# board2_schematic.net
KiCad netlist of a schematic drawn in Altium Designer
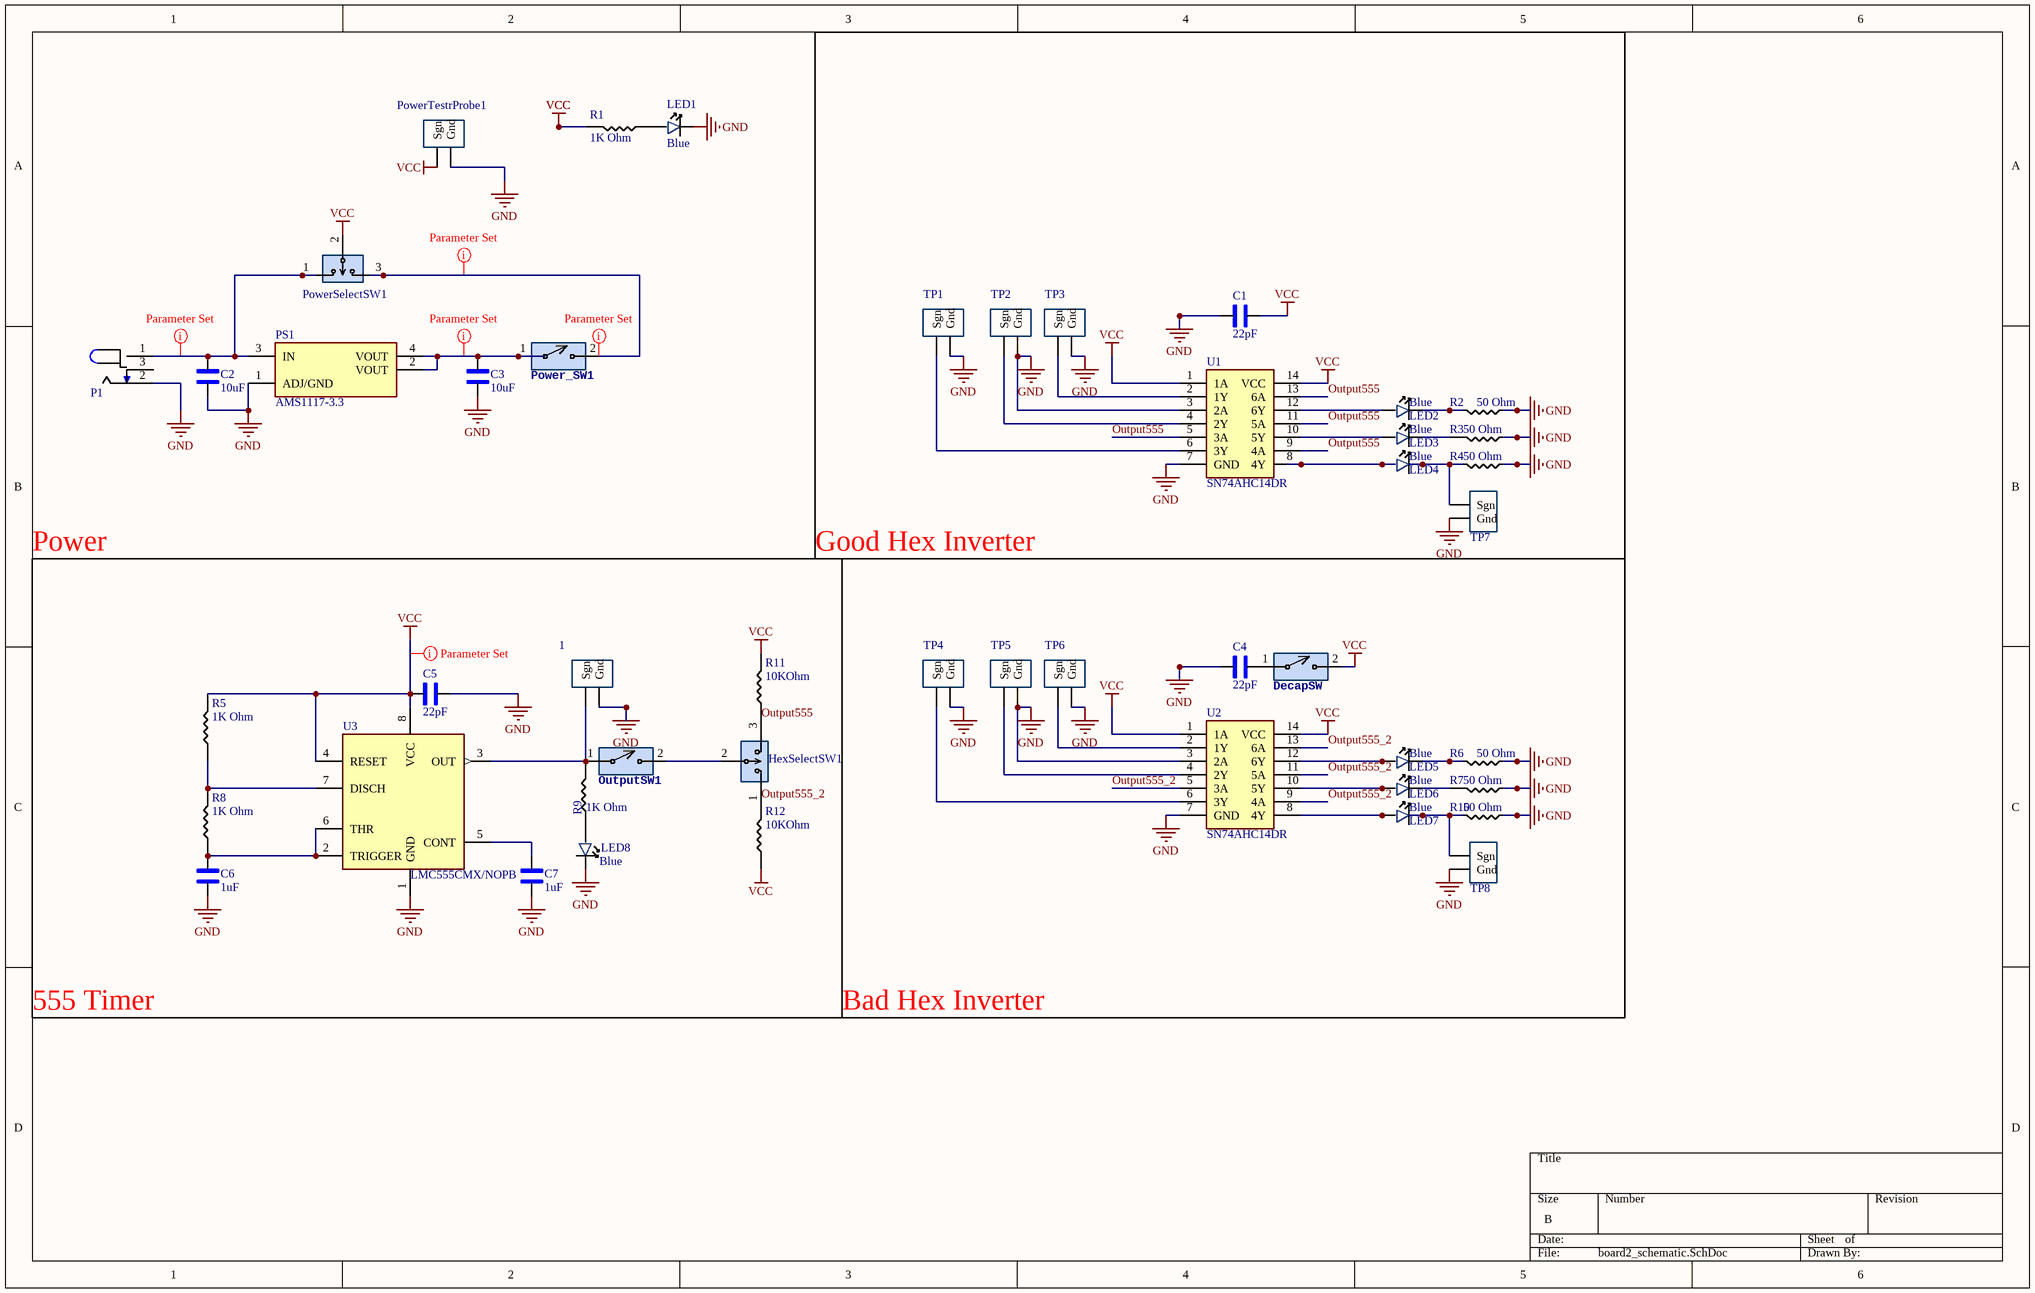
[diagram p0: board2_schematic.SchDoc]

(export (version "E")
  (design (tool "Eeschema 10.0.6"))
  (components
    (comp (ref "1")
      (value "10x Probe TP")
      (footprint "TP10x_Probe")
      (description "Test Point 300 mil centers")
      (libsource (lib "") (part "TP_10x_Probe_1"))
    )
    (comp (ref "C1")
      (value "22pF")
      (footprint "1206_Passive_Capacitor")
      (description "22pF ±5% 1kV C0G 1206 Multilayer Ceramic Capacitors MLCC - SMD/SMT RoHS")
      (fields (field (name "LCSC PART#") "C107174") (field (name "MFR PART #") "CC1206JKNPOCBN220"))
      (libsource (lib "ECEN5730Lib_2023_05_DS") (part "C_22pF_1206"))
    )
    (comp (ref "C2")
      (value "10uF")
      (footprint "1206_Passive_Capacitor")
      (description "10uF ±10% 50V X5R 1206 Multilayer Ceramic Capacitors MLCC - SMD/SMT RoHS")
      (fields (field (name "LCSC PART#") "C13585") (field (name "MFR PART #") "CL31A106KBHNNNE"))
      (libsource (lib "ECEN5730Lib_2023_05_DS") (part "C_10uF_1206"))
    )
    (comp (ref "C3")
      (value "10uF")
      (footprint "1206_Passive_Capacitor")
      (description "10uF ±10% 50V X5R 1206 Multilayer Ceramic Capacitors MLCC - SMD/SMT RoHS")
      (fields (field (name "LCSC PART#") "C13585") (field (name "MFR PART #") "CL31A106KBHNNNE"))
      (libsource (lib "ECEN5730Lib_2023_05_DS") (part "C_10uF_1206"))
    )
    (comp (ref "C4")
      (value "22pF")
      (footprint "1206_Passive_Capacitor")
      (description "22pF ±5% 1kV C0G 1206 Multilayer Ceramic Capacitors MLCC - SMD/SMT RoHS")
      (fields (field (name "LCSC PART#") "C107174") (field (name "MFR PART #") "CC1206JKNPOCBN220"))
      (libsource (lib "ECEN5730Lib_2023_05_DS") (part "C_22pF_1206"))
    )
    (comp (ref "C5")
      (value "22pF")
      (footprint "1206_Passive_Capacitor")
      (description "22pF ±5% 1kV C0G 1206 Multilayer Ceramic Capacitors MLCC - SMD/SMT RoHS")
      (fields (field (name "LCSC PART#") "C107174") (field (name "MFR PART #") "CC1206JKNPOCBN220"))
      (libsource (lib "ECEN5730Lib_2023_05_DS") (part "C_22pF_1206"))
    )
    (comp (ref "C6")
      (value "1uF")
      (footprint "1206_Passive_Capacitor")
      (description "MULTILAYER CERAMIC CAPACITORS MLCC - SMD/SMT 1UF 50V 1206 ROHS")
      (fields (field (name "MFR PART #") "CL31B105KBHNNNE") (field (name "LCSC PART#") "C1848"))
      (libsource (lib "ECEN5730Lib_2023_05_DS") (part "C_1uF_1206"))
    )
    (comp (ref "C7")
      (value "1uF")
      (footprint "1206_Passive_Capacitor")
      (description "MULTILAYER CERAMIC CAPACITORS MLCC - SMD/SMT 1UF 50V 1206 ROHS")
      (fields (field (name "MFR PART #") "CL31B105KBHNNNE") (field (name "LCSC PART#") "C1848"))
      (libsource (lib "ECEN5730Lib_2023_05_DS") (part "C_1uF_1206"))
    )
    (comp (ref "DecapSW")
      (value "SW_2Pin_100mil_Switch")
      (footprint "2Pin-Header-Conn")
      (description "2Pin Header")
      (fields (field (name "LCSC PART#") "C124375"))
      (libsource (lib "ECEN5730Lib_2023_05_DS") (part "SW_2Pin_100mil_Switch"))
    )
    (comp (ref "HexSelectSW1")
      (value "PREC003SAAN-RC")
      (footprint "3_PIN_100mil")
      (description "Connector Header Through Hole 3 position 0.100\" (2.54mm)")
      (fields (field (name "LCSC PART#") "C49257"))
      (libsource (lib "ECEN5730Lib_2023_05_DS") (part "SW_3Pin_100mil_Switch"))
    )
    (comp (ref "LED1")
      (value "Blue")
      (footprint "LED_1206")
      (description "blue 1206  Light Emitting Diodes (LED) ROHS")
      (fields (field (name "MFR PART #") "NCD1206B1") (field (name "LCSC PART#") "C130717"))
      (libsource (lib "ECEN5730Lib_2023_05_DS") (part "LED_BLUE_1206"))
    )
    (comp (ref "LED2")
      (value "Blue")
      (footprint "LED_1206")
      (description "blue 1206  Light Emitting Diodes (LED) ROHS")
      (fields (field (name "MFR PART #") "NCD1206B1") (field (name "LCSC PART#") "C130717"))
      (libsource (lib "ECEN5730Lib_2023_05_DS") (part "LED_BLUE_1206"))
    )
    (comp (ref "LED3")
      (value "Blue")
      (footprint "LED_1206")
      (description "blue 1206  Light Emitting Diodes (LED) ROHS")
      (fields (field (name "MFR PART #") "NCD1206B1") (field (name "LCSC PART#") "C130717"))
      (libsource (lib "ECEN5730Lib_2023_05_DS") (part "LED_BLUE_1206"))
    )
    (comp (ref "LED4")
      (value "Blue")
      (footprint "LED_1206")
      (description "blue 1206  Light Emitting Diodes (LED) ROHS")
      (fields (field (name "MFR PART #") "NCD1206B1") (field (name "LCSC PART#") "C130717"))
      (libsource (lib "ECEN5730Lib_2023_05_DS") (part "LED_BLUE_1206"))
    )
    (comp (ref "LED5")
      (value "Blue")
      (footprint "LED_1206")
      (description "blue 1206  Light Emitting Diodes (LED) ROHS")
      (fields (field (name "MFR PART #") "NCD1206B1") (field (name "LCSC PART#") "C130717"))
      (libsource (lib "ECEN5730Lib_2023_05_DS") (part "LED_BLUE_1206"))
    )
    (comp (ref "LED6")
      (value "Blue")
      (footprint "LED_1206")
      (description "blue 1206  Light Emitting Diodes (LED) ROHS")
      (fields (field (name "MFR PART #") "NCD1206B1") (field (name "LCSC PART#") "C130717"))
      (libsource (lib "ECEN5730Lib_2023_05_DS") (part "LED_BLUE_1206"))
    )
    (comp (ref "LED7")
      (value "Blue")
      (footprint "LED_1206")
      (description "blue 1206  Light Emitting Diodes (LED) ROHS")
      (fields (field (name "MFR PART #") "NCD1206B1") (field (name "LCSC PART#") "C130717"))
      (libsource (lib "ECEN5730Lib_2023_05_DS") (part "LED_BLUE_1206"))
    )
    (comp (ref "LED8")
      (value "Blue")
      (footprint "LED_1206")
      (description "blue 1206  Light Emitting Diodes (LED) ROHS")
      (fields (field (name "MFR PART #") "NCD1206B1") (field (name "LCSC PART#") "C130717"))
      (libsource (lib "ECEN5730Lib_2023_05_DS") (part "LED_BLUE_1206"))
    )
    (comp (ref "OutputSW1")
      (value "SW_2Pin_100mil_Switch")
      (footprint "2Pin-Header-Conn")
      (description "2Pin Header")
      (fields (field (name "LCSC PART#") "C124375"))
      (libsource (lib "ECEN5730Lib_2023_05_DS") (part "SW_2Pin_100mil_Switch"))
    )
    (comp (ref "P1")
      (value "Power Jack")
      (footprint "Power_Jack")
      (description "Power Barrel Connector Jack 2.10mm ID (0.083\"), 5.50mm OD (0.217\") Through Hole, Right Angle")
      (fields (field (name "MFR PART #") "PJ-102A") (field (name "LCSC PART#") "C136744"))
      (libsource (lib "ECEN5730Lib_2023_05_DS") (part "P_Power Jack"))
    )
    (comp (ref "PowerSelectSW1")
      (value "PREC003SAAN-RC")
      (footprint "3_PIN_100mil")
      (description "Connector Header Through Hole 3 position 0.100\" (2.54mm)")
      (fields (field (name "LCSC PART#") "C49257"))
      (libsource (lib "") (part "SW_3Pin_100mil_Switch_1"))
    )
    (comp (ref "PowerTestrProbe1")
      (value "10x Probe TP")
      (footprint "TP10x_Probe")
      (description "Test Point 300 mil centers")
      (libsource (lib "") (part "TP_10x_Probe_1"))
    )
    (comp (ref "Power_SW1")
      (value "SW_2Pin_100mil_Switch")
      (footprint "2Pin-Header-Conn")
      (description "2Pin Header")
      (fields (field (name "LCSC PART#") "C124375"))
      (libsource (lib "ECEN5730Lib_2023_05_DS") (part "SW_2Pin_100mil_Switch"))
    )
    (comp (ref "PS1")
      (value "AMS1117-3.3")
      (footprint "LDO")
      (description "LOW DROPOUT REGULATORS(LDO) POSITIVE FIXED 1.3V @ 800MA 15V 3.3V 1A SOT-223 ROHS")
      (fields (field (name "LCSC PART#") "C6186"))
      (libsource (lib "ECEN5730Lib_2023_05_DS") (part "PS_AMS_LDO_3v3"))
    )
    (comp (ref "R1")
      (value "1K Ohm")
      (footprint "1206_Passive_Resitor")
      (description "CHIP RESISTOR - SURFACE MOUNT 1KOHMS ±1% 1/4W 1206 ROHS")
      (fields (field (name "MFR PART #") "RNCP1206FTD1K00CT") (field (name "LCSC PART#") "C4410"))
      (libsource (lib "ECEN5730Lib_2023_05_DS") (part "R_1K_1206"))
    )
    (comp (ref "R2")
      (value "50 Ohm")
      (footprint "1206_Passive_Resitor")
      (description "CHIP RESISTOR - SURFACE MOUNT 50OHMS ±1% 1/4W 1206 ROHS")
      (fields (field (name "MFR PART #") "RNCP1206FTD1K00CT") (field (name "LCSC PART#") "C4410"))
      (libsource (lib "ECEN5730Lib_2023_05_DS") (part "R_1K_1206"))
    )
    (comp (ref "R3")
      (value "50 Ohm")
      (footprint "1206_Passive_Resitor")
      (description "CHIP RESISTOR - SURFACE MOUNT 50OHMS ±1% 1/4W 1206 ROHS")
      (fields (field (name "MFR PART #") "RNCP1206FTD1K00CT") (field (name "LCSC PART#") "C4410"))
      (libsource (lib "ECEN5730Lib_2023_05_DS") (part "R_1K_1206"))
    )
    (comp (ref "R4")
      (value "50 Ohm")
      (footprint "1206_Passive_Resitor")
      (description "CHIP RESISTOR - SURFACE MOUNT 50OHMS ±1% 1/4W 1206 ROHS")
      (fields (field (name "MFR PART #") "RNCP1206FTD1K00CT") (field (name "LCSC PART#") "C4410"))
      (libsource (lib "ECEN5730Lib_2023_05_DS") (part "R_1K_1206"))
    )
    (comp (ref "R5")
      (value "1K Ohm")
      (footprint "1206_Passive_Resitor")
      (description "CHIP RESISTOR - SURFACE MOUNT 1KOHMS ±1% 1/4W 1206 ROHS")
      (fields (field (name "MFR PART #") "RNCP1206FTD1K00CT") (field (name "LCSC PART#") "C4410"))
      (libsource (lib "ECEN5730Lib_2023_05_DS") (part "R_1K_1206"))
    )
    (comp (ref "R6")
      (value "50 Ohm")
      (footprint "1206_Passive_Resitor")
      (description "CHIP RESISTOR - SURFACE MOUNT 50OHMS ±1% 1/4W 1206 ROHS")
      (fields (field (name "MFR PART #") "RNCP1206FTD1K00CT") (field (name "LCSC PART#") "C4410"))
      (libsource (lib "ECEN5730Lib_2023_05_DS") (part "R_1K_1206"))
    )
    (comp (ref "R7")
      (value "50 Ohm")
      (footprint "1206_Passive_Resitor")
      (description "CHIP RESISTOR - SURFACE MOUNT 50OHMS ±1% 1/4W 1206 ROHS")
      (fields (field (name "MFR PART #") "RNCP1206FTD1K00CT") (field (name "LCSC PART#") "C4410"))
      (libsource (lib "ECEN5730Lib_2023_05_DS") (part "R_1K_1206"))
    )
    (comp (ref "R8")
      (value "1K Ohm")
      (footprint "1206_Passive_Resitor")
      (description "CHIP RESISTOR - SURFACE MOUNT 1KOHMS ±1% 1/4W 1206 ROHS")
      (fields (field (name "MFR PART #") "RNCP1206FTD1K00CT") (field (name "LCSC PART#") "C4410"))
      (libsource (lib "ECEN5730Lib_2023_05_DS") (part "R_1K_1206"))
    )
    (comp (ref "R9")
      (value "1K Ohm")
      (footprint "1206_Passive_Resitor")
      (description "CHIP RESISTOR - SURFACE MOUNT 1KOHMS ±1% 1/4W 1206 ROHS")
      (fields (field (name "MFR PART #") "RNCP1206FTD1K00CT") (field (name "LCSC PART#") "C4410"))
      (libsource (lib "ECEN5730Lib_2023_05_DS") (part "R_1K_1206"))
    )
    (comp (ref "R10")
      (value "50 Ohm")
      (footprint "1206_Passive_Resitor")
      (description "CHIP RESISTOR - SURFACE MOUNT 50OHMS ±1% 1/4W 1206 ROHS")
      (fields (field (name "MFR PART #") "RNCP1206FTD1K00CT") (field (name "LCSC PART#") "C4410"))
      (libsource (lib "ECEN5730Lib_2023_05_DS") (part "R_1K_1206"))
    )
    (comp (ref "R11")
      (value "10KOhm")
      (footprint "1206_Passive_Resitor")
      (description "10 kOhms ±5% 0.25W, 1/4W Chip Resistor 1206 (3216 Metric) Automotive AEC-Q200 Thick Film")
      (fields (field (name "MFR PART #") "RMCF1206FT10K0") (field (name "LCSC PART#") "C17902"))
      (libsource (lib "ECEN5730Lib_2023_05_DS") (part "R_10KOhm_1206"))
    )
    (comp (ref "R12")
      (value "10KOhm")
      (footprint "1206_Passive_Resitor")
      (description "10 kOhms ±5% 0.25W, 1/4W Chip Resistor 1206 (3216 Metric) Automotive AEC-Q200 Thick Film")
      (fields (field (name "MFR PART #") "RMCF1206FT10K0") (field (name "LCSC PART#") "C17902"))
      (libsource (lib "ECEN5730Lib_2023_05_DS") (part "R_10KOhm_1206"))
    )
    (comp (ref "TP1")
      (value "10x Probe TP")
      (footprint "TP10x_Probe")
      (description "Test Point 300 mil centers")
      (libsource (lib "") (part "TP_10x_Probe_1"))
    )
    (comp (ref "TP2")
      (value "10x Probe TP")
      (footprint "TP10x_Probe")
      (description "Test Point 300 mil centers")
      (libsource (lib "") (part "TP_10x_Probe_1"))
    )
    (comp (ref "TP3")
      (value "10x Probe TP")
      (footprint "TP10x_Probe")
      (description "Test Point 300 mil centers")
      (libsource (lib "") (part "TP_10x_Probe_1"))
    )
    (comp (ref "TP4")
      (value "10x Probe TP")
      (footprint "TP10x_Probe")
      (description "Test Point 300 mil centers")
      (libsource (lib "") (part "TP_10x_Probe_1"))
    )
    (comp (ref "TP5")
      (value "10x Probe TP")
      (footprint "TP10x_Probe")
      (description "Test Point 300 mil centers")
      (libsource (lib "") (part "TP_10x_Probe_1"))
    )
    (comp (ref "TP6")
      (value "10x Probe TP")
      (footprint "TP10x_Probe")
      (description "Test Point 300 mil centers")
      (libsource (lib "") (part "TP_10x_Probe_1"))
    )
    (comp (ref "TP7")
      (value "10x Probe TP")
      (footprint "TP10x_Probe")
      (description "Test Point 300 mil centers")
      (libsource (lib "ECEN5730Lib_2023_05_DS") (part "TP_10x_Probe"))
    )
    (comp (ref "TP8")
      (value "10x Probe TP")
      (footprint "TP10x_Probe")
      (description "Test Point 300 mil centers")
      (libsource (lib "ECEN5730Lib_2023_05_DS") (part "TP_10x_Probe"))
    )
    (comp (ref "U1")
      (value "SN74AHC14DR")
      (footprint "HEX_74AC14")
      (description "Inverter IC 6 Channel Schmitt Trigger 14-SOIC")
      (fields (field (name "LCSC PART#") "C6942"))
      (libsource (lib "ECEN5730Lib_2023_05_DS") (part "U_74AHC14"))
    )
    (comp (ref "U2")
      (value "SN74AHC14DR")
      (footprint "HEX_74AC14")
      (description "Inverter IC 6 Channel Schmitt Trigger 14-SOIC")
      (fields (field (name "LCSC PART#") "C6942"))
      (libsource (lib "ECEN5730Lib_2023_05_DS") (part "U_74AHC14"))
    )
    (comp (ref "U3")
      (value "LMC555CMX/NOPB")
      (footprint "TS555IDTTR")
      (description "555 Type, Timer/Oscillator _Single_ IC 3MHz 8-SO")
      (fields (field (name "LCSC PART#") "C90760"))
      (libsource (lib "ECEN5730Lib_2023_05_DS") (part "U_555_Fast"))
    )
  )
  (nets
    (net (code "1") (name "/Output555") (class "Default")
      (node (ref "HexSelectSW1") (pin "3") (pinfunction "3_3") (pintype "passive"))
      (node (ref "R11") (pin "1") (pinfunction "1_1") (pintype "passive"))
      (node (ref "U1") (pin "11") (pinfunction "5A_11") (pintype "passive"))
      (node (ref "U1") (pin "13") (pinfunction "6A_13") (pintype "passive"))
      (node (ref "U1") (pin "5") (pinfunction "3A_5") (pintype "passive"))
      (node (ref "U1") (pin "9") (pinfunction "4A_9") (pintype "passive"))
    )
    (net (code "2") (name "/Output555_2") (class "Default")
      (node (ref "HexSelectSW1") (pin "1") (pinfunction "1_1") (pintype "passive"))
      (node (ref "R12") (pin "2") (pinfunction "2_2") (pintype "passive"))
      (node (ref "U2") (pin "11") (pinfunction "5A_11") (pintype "passive"))
      (node (ref "U2") (pin "13") (pinfunction "6A_13") (pintype "passive"))
      (node (ref "U2") (pin "5") (pinfunction "3A_5") (pintype "passive"))
      (node (ref "U2") (pin "9") (pinfunction "4A_9") (pintype "passive"))
    )
    (net (code "3") (name "GND") (class "Default")
      (node (ref "1") (pin "2") (pinfunction "Gnd_2") (pintype "passive"))
      (node (ref "C1") (pin "1") (pinfunction "1_1") (pintype "passive"))
      (node (ref "C2") (pin "1") (pinfunction "1_1") (pintype "passive"))
      (node (ref "C3") (pin "1") (pinfunction "1_1") (pintype "passive"))
      (node (ref "C4") (pin "1") (pinfunction "1_1") (pintype "passive"))
      (node (ref "C5") (pin "2") (pinfunction "2_2") (pintype "passive"))
      (node (ref "C6") (pin "1") (pinfunction "1_1") (pintype "passive"))
      (node (ref "C7") (pin "1") (pinfunction "1_1") (pintype "passive"))
      (node (ref "LED1") (pin "2") (pinfunction "2_2") (pintype "passive"))
      (node (ref "LED8") (pin "2") (pinfunction "2_2") (pintype "passive"))
      (node (ref "P1") (pin "2") (pinfunction "2_2") (pintype "power_in"))
      (node (ref "PS1") (pin "1") (pinfunction "ADJ/GND_1") (pintype "passive"))
      (node (ref "PowerTestrProbe1") (pin "2") (pinfunction "Gnd_2") (pintype "passive"))
      (node (ref "R10") (pin "1") (pinfunction "1_1") (pintype "passive"))
      (node (ref "R2") (pin "1") (pinfunction "1_1") (pintype "passive"))
      (node (ref "R3") (pin "1") (pinfunction "1_1") (pintype "passive"))
      (node (ref "R4") (pin "1") (pinfunction "1_1") (pintype "passive"))
      (node (ref "R6") (pin "1") (pinfunction "1_1") (pintype "passive"))
      (node (ref "R7") (pin "1") (pinfunction "1_1") (pintype "passive"))
      (node (ref "TP1") (pin "2") (pinfunction "Gnd_2") (pintype "passive"))
      (node (ref "TP2") (pin "2") (pinfunction "Gnd_2") (pintype "passive"))
      (node (ref "TP3") (pin "2") (pinfunction "Gnd_2") (pintype "passive"))
      (node (ref "TP4") (pin "2") (pinfunction "Gnd_2") (pintype "passive"))
      (node (ref "TP5") (pin "2") (pinfunction "Gnd_2") (pintype "passive"))
      (node (ref "TP6") (pin "2") (pinfunction "Gnd_2") (pintype "passive"))
      (node (ref "TP7") (pin "2") (pinfunction "Gnd_2") (pintype "passive"))
      (node (ref "TP8") (pin "2") (pinfunction "Gnd_2") (pintype "passive"))
      (node (ref "U1") (pin "3") (pinfunction "2A_3") (pintype "passive"))
      (node (ref "U1") (pin "7") (pinfunction "GND_7") (pintype "passive"))
      (node (ref "U2") (pin "3") (pinfunction "2A_3") (pintype "passive"))
      (node (ref "U2") (pin "7") (pinfunction "GND_7") (pintype "passive"))
      (node (ref "U3") (pin "1") (pinfunction "GND_1") (pintype "power_in"))
    )
    (net (code "4") (name "Net-(1-Sgn)") (class "Default")
      (node (ref "1") (pin "1") (pinfunction "Sgn_1") (pintype "passive"))
      (node (ref "OutputSW1") (pin "1") (pinfunction "1_1") (pintype "passive"))
      (node (ref "R9") (pin "2") (pinfunction "2_2") (pintype "passive"))
      (node (ref "U3") (pin "3") (pinfunction "OUT_3") (pintype "output"))
    )
    (net (code "5") (name "Net-(C3-Pad2)") (class "Default")
      (node (ref "C3") (pin "2") (pinfunction "2_2") (pintype "passive"))
      (node (ref "PS1") (pin "2") (pinfunction "VOUT_2") (pintype "power_in"))
      (node (ref "PS1") (pin "4") (pinfunction "VOUT_4") (pintype "power_in"))
      (node (ref "Power_SW1") (pin "1") (pinfunction "1_1") (pintype "passive"))
    )
    (net (code "6") (name "Net-(C4-Pad2)") (class "Default")
      (node (ref "C4") (pin "2") (pinfunction "2_2") (pintype "passive"))
      (node (ref "DecapSW") (pin "1") (pinfunction "1_1") (pintype "passive"))
    )
    (net (code "7") (name "Net-(HexSelectSW1-Pad2)") (class "Default")
      (node (ref "HexSelectSW1") (pin "2") (pinfunction "2_2") (pintype "passive"))
      (node (ref "OutputSW1") (pin "2") (pinfunction "2_2") (pintype "passive"))
    )
    (net (code "8") (name "Net-(LED1-Pad1)") (class "Default")
      (node (ref "LED1") (pin "1") (pinfunction "1_1") (pintype "passive"))
      (node (ref "R1") (pin "1") (pinfunction "1_1") (pintype "passive"))
    )
    (net (code "9") (name "Net-(LED2-Pad2)") (class "Default")
      (node (ref "LED2") (pin "2") (pinfunction "2_2") (pintype "passive"))
      (node (ref "R2") (pin "2") (pinfunction "2_2") (pintype "passive"))
    )
    (net (code "10") (name "Net-(LED3-Pad2)") (class "Default")
      (node (ref "LED3") (pin "2") (pinfunction "2_2") (pintype "passive"))
      (node (ref "R3") (pin "2") (pinfunction "2_2") (pintype "passive"))
    )
    (net (code "11") (name "Net-(LED5-Pad2)") (class "Default")
      (node (ref "LED5") (pin "2") (pinfunction "2_2") (pintype "passive"))
      (node (ref "R6") (pin "2") (pinfunction "2_2") (pintype "passive"))
    )
    (net (code "12") (name "Net-(LED6-Pad2)") (class "Default")
      (node (ref "LED6") (pin "2") (pinfunction "2_2") (pintype "passive"))
      (node (ref "R7") (pin "2") (pinfunction "2_2") (pintype "passive"))
    )
    (net (code "13") (name "Net-(LED8-Pad1)") (class "Default")
      (node (ref "LED8") (pin "1") (pinfunction "1_1") (pintype "passive"))
      (node (ref "R9") (pin "1") (pinfunction "1_1") (pintype "passive"))
    )
    (net (code "14") (name "Net-(PS1-IN)") (class "Default")
      (node (ref "C2") (pin "2") (pinfunction "2_2") (pintype "passive"))
      (node (ref "P1") (pin "1") (pinfunction "1_1") (pintype "power_in"))
      (node (ref "PS1") (pin "3") (pinfunction "IN_3") (pintype "power_in"))
      (node (ref "PowerSelectSW1") (pin "1") (pinfunction "1_1") (pintype "passive"))
    )
    (net (code "15") (name "Net-(PowerSelectSW1-Pad3)") (class "Default")
      (node (ref "PowerSelectSW1") (pin "3") (pinfunction "3_3") (pintype "passive"))
      (node (ref "Power_SW1") (pin "2") (pinfunction "2_2") (pintype "passive"))
    )
    (net (code "16") (name "Net-(TP1-Sgn)") (class "Default")
      (node (ref "TP1") (pin "1") (pinfunction "Sgn_1") (pintype "passive"))
      (node (ref "U1") (pin "6") (pinfunction "3Y_6") (pintype "passive"))
    )
    (net (code "17") (name "Net-(TP2-Sgn)") (class "Default")
      (node (ref "TP2") (pin "1") (pinfunction "Sgn_1") (pintype "passive"))
      (node (ref "U1") (pin "4") (pinfunction "2Y_4") (pintype "passive"))
    )
    (net (code "18") (name "Net-(TP3-Sgn)") (class "Default")
      (node (ref "TP3") (pin "1") (pinfunction "Sgn_1") (pintype "passive"))
      (node (ref "U1") (pin "2") (pinfunction "1Y_2") (pintype "passive"))
    )
    (net (code "19") (name "Net-(TP4-Sgn)") (class "Default")
      (node (ref "TP4") (pin "1") (pinfunction "Sgn_1") (pintype "passive"))
      (node (ref "U2") (pin "6") (pinfunction "3Y_6") (pintype "passive"))
    )
    (net (code "20") (name "Net-(TP5-Sgn)") (class "Default")
      (node (ref "TP5") (pin "1") (pinfunction "Sgn_1") (pintype "passive"))
      (node (ref "U2") (pin "4") (pinfunction "2Y_4") (pintype "passive"))
    )
    (net (code "21") (name "Net-(TP6-Sgn)") (class "Default")
      (node (ref "TP6") (pin "1") (pinfunction "Sgn_1") (pintype "passive"))
      (node (ref "U2") (pin "2") (pinfunction "1Y_2") (pintype "passive"))
    )
    (net (code "22") (name "Net-(TP7-Sgn)") (class "Default")
      (node (ref "LED4") (pin "2") (pinfunction "2_2") (pintype "passive"))
      (node (ref "R4") (pin "2") (pinfunction "2_2") (pintype "passive"))
      (node (ref "TP7") (pin "1") (pinfunction "Sgn_1") (pintype "passive"))
    )
    (net (code "23") (name "Net-(TP8-Sgn)") (class "Default")
      (node (ref "LED7") (pin "2") (pinfunction "2_2") (pintype "passive"))
      (node (ref "R10") (pin "2") (pinfunction "2_2") (pintype "passive"))
      (node (ref "TP8") (pin "1") (pinfunction "Sgn_1") (pintype "passive"))
    )
    (net (code "24") (name "Net-(U1-4Y)") (class "Default")
      (node (ref "LED4") (pin "1") (pinfunction "1_1") (pintype "passive"))
      (node (ref "U1") (pin "8") (pinfunction "4Y_8") (pintype "passive"))
    )
    (net (code "25") (name "Net-(U1-5Y)") (class "Default")
      (node (ref "LED3") (pin "1") (pinfunction "1_1") (pintype "passive"))
      (node (ref "U1") (pin "10") (pinfunction "5Y_10") (pintype "passive"))
    )
    (net (code "26") (name "Net-(U1-6Y)") (class "Default")
      (node (ref "LED2") (pin "1") (pinfunction "1_1") (pintype "passive"))
      (node (ref "U1") (pin "12") (pinfunction "6Y_12") (pintype "passive"))
    )
    (net (code "27") (name "Net-(U2-4Y)") (class "Default")
      (node (ref "LED7") (pin "1") (pinfunction "1_1") (pintype "passive"))
      (node (ref "U2") (pin "8") (pinfunction "4Y_8") (pintype "passive"))
    )
    (net (code "28") (name "Net-(U2-5Y)") (class "Default")
      (node (ref "LED6") (pin "1") (pinfunction "1_1") (pintype "passive"))
      (node (ref "U2") (pin "10") (pinfunction "5Y_10") (pintype "passive"))
    )
    (net (code "29") (name "Net-(U2-6Y)") (class "Default")
      (node (ref "LED5") (pin "1") (pinfunction "1_1") (pintype "passive"))
      (node (ref "U2") (pin "12") (pinfunction "6Y_12") (pintype "passive"))
    )
    (net (code "30") (name "Net-(U3-CONT)") (class "Default")
      (node (ref "C7") (pin "2") (pinfunction "2_2") (pintype "passive"))
      (node (ref "U3") (pin "5") (pinfunction "CONT_5") (pintype "passive"))
    )
    (net (code "31") (name "Net-(U3-DISCH)") (class "Default")
      (node (ref "R5") (pin "1") (pinfunction "1_1") (pintype "passive"))
      (node (ref "R8") (pin "2") (pinfunction "2_2") (pintype "passive"))
      (node (ref "U3") (pin "7") (pinfunction "DISCH_7") (pintype "passive"))
    )
    (net (code "32") (name "Net-(U3-THR)") (class "Default")
      (node (ref "C6") (pin "2") (pinfunction "2_2") (pintype "passive"))
      (node (ref "R8") (pin "1") (pinfunction "1_1") (pintype "passive"))
      (node (ref "U3") (pin "2") (pinfunction "TRIGGER_2") (pintype "passive"))
      (node (ref "U3") (pin "6") (pinfunction "THR_6") (pintype "passive"))
    )
    (net (code "33") (name "VCC") (class "Default")
      (node (ref "C1") (pin "2") (pinfunction "2_2") (pintype "passive"))
      (node (ref "C5") (pin "1") (pinfunction "1_1") (pintype "passive"))
      (node (ref "DecapSW") (pin "2") (pinfunction "2_2") (pintype "passive"))
      (node (ref "PowerSelectSW1") (pin "2") (pinfunction "2_2") (pintype "passive"))
      (node (ref "PowerTestrProbe1") (pin "1") (pinfunction "Sgn_1") (pintype "passive"))
      (node (ref "R1") (pin "2") (pinfunction "2_2") (pintype "passive"))
      (node (ref "R11") (pin "2") (pinfunction "2_2") (pintype "passive"))
      (node (ref "R12") (pin "1") (pinfunction "1_1") (pintype "passive"))
      (node (ref "R5") (pin "2") (pinfunction "2_2") (pintype "passive"))
      (node (ref "U1") (pin "1") (pinfunction "1A_1") (pintype "passive"))
      (node (ref "U1") (pin "14") (pinfunction "VCC_14") (pintype "passive"))
      (node (ref "U2") (pin "1") (pinfunction "1A_1") (pintype "passive"))
      (node (ref "U2") (pin "14") (pinfunction "VCC_14") (pintype "passive"))
      (node (ref "U3") (pin "4") (pinfunction "RESET_4") (pintype "passive"))
      (node (ref "U3") (pin "8") (pinfunction "VCC_8") (pintype "power_in"))
    )
    (net (code "34") (name "unconnected-(P1-Pad3)") (class "Default")
      (node (ref "P1") (pin "3") (pinfunction "3_3") (pintype "power_in"))
    )
  )
)
